# Power.net
KiCad netlist of a schematic drawn in Altium Designer
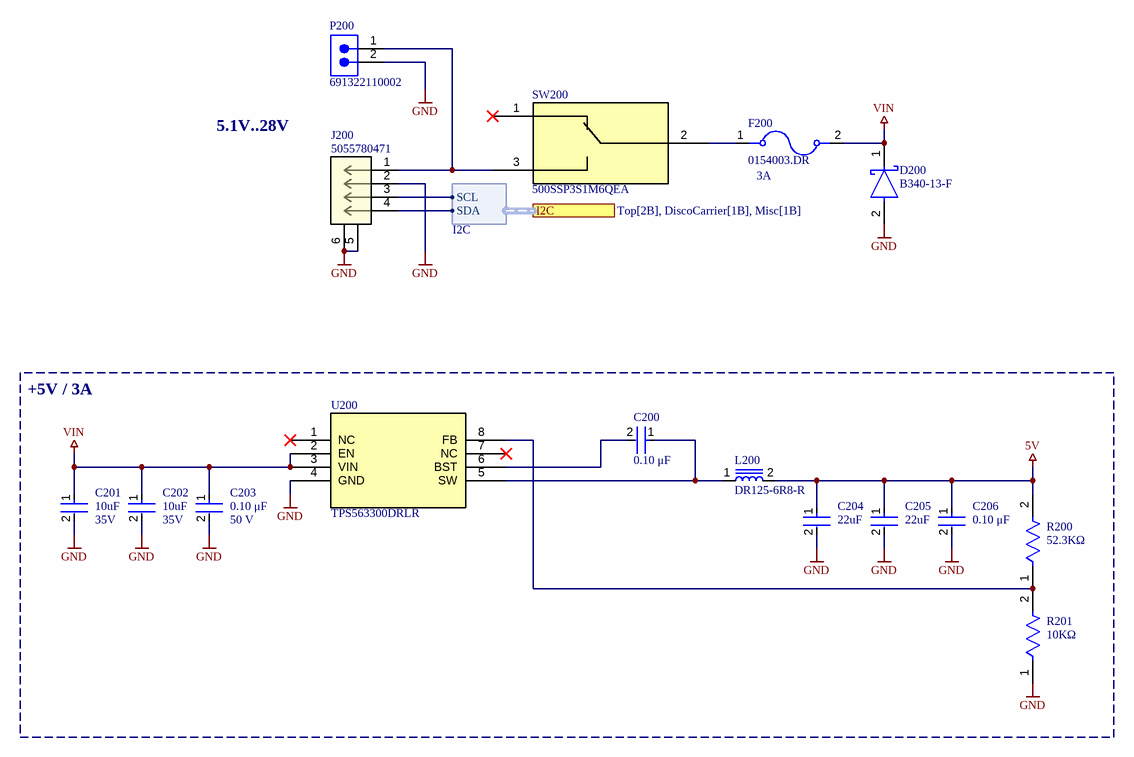
[diagram p0: Power.SchDoc]

(export (version "E")
  (design (tool "Eeschema 10.0.6"))
  (components
    (comp (ref "C200")
      (value "0.10 μF")
      (footprint "FP-C0603C-CF-MFG")
      (description "CAP CER 0.1UF 50V 20% X7R 0603")
      (fields
        (field (name "MANUFACTURER PART NUMBER") "C0603C104M5RACTU")
        (field (name "MANUFACTURER") "KEMET")
      )
      (libsource (lib "Altium Content Vault") (part "b4654b650e69147ec39a6b967a45e02"))
    )
    (comp (ref "C201")
      (value "GRT31CR6YA106KE01L")
      (footprint "FP-GRT31C-0_2-IPC_A")
      (description "Multi-Layer Ceramic Capacitor 10uF 35V X5R ±10% 1206 Emboss T/R")
      (fields
        (field (name "CAPACITANCE") "10uF")
        (field (name "TOLERANCE") "10%")
        (field (name "VOLTAGE RATING") "35V")
      )
      (libsource (lib "Altium Content Vault") (part "02cd4be3c70576c341d710602a673aa"))
    )
    (comp (ref "C202")
      (value "GRT31CR6YA106KE01L")
      (footprint "FP-GRT31C-0_2-IPC_A")
      (description "Multi-Layer Ceramic Capacitor 10uF 35V X5R ±10% 1206 Emboss T/R")
      (fields
        (field (name "CAPACITANCE") "10uF")
        (field (name "TOLERANCE") "10%")
        (field (name "VOLTAGE RATING") "35V")
      )
      (libsource (lib "Altium Content Vault") (part "02cd4be3c70576c341d710602a673aa"))
    )
    (comp (ref "C203")
      (value "0.10 μF")
      (footprint "FP-C0603C-CF-MFG")
      (description "CAP CER 0.1UF 50V 20% X7R 0603")
      (fields
        (field (name "VOLTAGE RATING") "50 V")
        (field (name "MANUFACTURER PART NUMBER") "C0603C104M5RACTU")
        (field (name "MANUFACTURER") "KEMET")
      )
      (libsource (lib "Altium Content Vault") (part "b4654b650e69147ec39a6b967a45e02"))
    )
    (comp (ref "C204")
      (value "GRM319R61C226ME15D")
      (footprint "FP-GRM319-0_15-IPC_C")
      (description "Chip Multilayer Ceramic Capacitors for General Purpose, 1206, 22uF, X5R, 15%, 20%, 16V")
      (fields (field (name "TOLERANCE") "20%") (field (name "CAPACITANCE") "22uF"))
      (libsource (lib "Altium Content Vault") (part "b4654b650e69147ec39a6b967a45e02"))
    )
    (comp (ref "C205")
      (value "GRM319R61C226ME15D")
      (footprint "FP-GRM319-0_15-IPC_C")
      (description "Chip Multilayer Ceramic Capacitors for General Purpose, 1206, 22uF, X5R, 15%, 20%, 16V")
      (fields (field (name "TOLERANCE") "20%") (field (name "CAPACITANCE") "22uF"))
      (libsource (lib "Altium Content Vault") (part "b4654b650e69147ec39a6b967a45e02"))
    )
    (comp (ref "C206")
      (value "0.10 μF")
      (footprint "FP-C0603C-CF-MFG")
      (description "CAP CER 0.1UF 50V 20% X7R 0603")
      (fields
        (field (name "MANUFACTURER PART NUMBER") "C0603C104M5RACTU")
        (field (name "MANUFACTURER") "KEMET")
      )
      (libsource (lib "Altium Content Vault") (part "b4654b650e69147ec39a6b967a45e02"))
    )
    (comp (ref "D200")
      (value "B340-13-F")
      (footprint "FP-SMC-MFG")
      (description "DIODE SCHOTTKY 40V 3A SMC")
      (fields
        (field (name "MANUFACTURER") "Diodes Inc.")
        (field (name "OCTOPART") "https://octopart.com/b340-13-f-diodes+inc.-325814")
      )
      (libsource (lib "Altium Content Vault") (part "1d6ec82d83fb6aee721767c19dac4b9"))
    )
    (comp (ref "F200")
      (value "0154003.DR")
      (footprint "FUSE_0154003.DR")
      (description "Nano2 SMD FF submin fuse w/holder, 3A ¦ Littelfuse 0154003.DR")
      (fields (field (name "ALTIUM_VALUE") "3A") (field (name "MF") "Littelfuse Inc."))
      (libsource (lib "robby") (part "0154003.DR"))
    )
    (comp (ref "J200")
      (value "5055780471")
      (footprint "CONN_505578_04_MOL")
      (fields (field (name "COPYRIGHT") "Copyright (C) 2025 Ultra Librarian. All rights reserved."))
      (libsource (lib "robby") (part "5055780471"))
    )
    (comp (ref "L200")
      (value "DR125-6R8-R")
      (footprint "robby:INDM1250X1250X600")
      (description "Inductor Power Shielded Drum Core 3.084u(OCL)H/3.3uH 20% 100KHz Ferrite 9.26A 6.3mOhm DCR T/R")
      (libsource (lib "robby") (part "DR125-6R8-R"))
    )
    (comp (ref "P200")
      (value "691322110002")
      (footprint "691322110002")
      (fields (field (name "VOLTAGE") "300V"))
      (libsource (lib "Altium Content Vault") (part "TBL - 1R - 02P - Male"))
    )
    (comp (ref "R200")
      (value "52.3KΩ")
      (footprint "FP-RT0603-MFG")
      (description "RES SMD 52.3K OHM 1% 1/10W 0603")
      (fields
        (field (name "MANUFACTURER PART NUMBER") "RT0603FRE0752K3L")
        (field (name "MANUFACTURER") "Yageo")
      )
      (libsource (lib "Altium Content Vault") (part "1029c3af85768c4190bb7ad29bc67b5"))
    )
    (comp (ref "R201")
      (value "10KΩ")
      (footprint "FP-RT0603-MFG")
      (description "RES SMD 10K OHM 1% 1/10W 0603")
      (fields
        (field (name "MANUFACTURER") "Yageo")
        (field (name "OCTOPART") "https://octopart.com/rt0603fre0710kl-yageo-40009243")
      )
      (libsource (lib "Altium Content Vault") (part "1029c3af85768c4190bb7ad29bc67b5"))
    )
    (comp (ref "SW200")
      (value "500SSP3S1M6QEA")
      (footprint "SW3_500SSP3S1M6QEA_EWI")
      (description "No Description Available")
      (fields (field (name "COPYRIGHT") "Copyright (C) 2025 Ultra Librarian. All rights reserved."))
      (libsource (lib "robby") (part "500SSP3S1M6QEA"))
    )
    (comp (ref "U200")
      (value "TPS563300DRLR")
      (footprint "SOT5X3-8_DRL_TEX")
      (description "3.8-V to 28-V Input, 3-A synchronous buck converter in SOT-583 package 8-SOT-5X3 -40 to 150")
      (fields (field (name "COPYRIGHT") "Copyright (C) 2025 Ultra Librarian. All rights reserved."))
      (libsource (lib "robby") (part "TPS563300DRLR"))
    )
  )
  (nets
    (net (code "2") (name "/SCL") (class "Default")
      (node (ref "J200") (pin "3") (pinfunction "3_3") (pintype "passive"))
    )
    (net (code "3") (name "/SDA") (class "Default")
      (node (ref "J200") (pin "4") (pinfunction "4_4") (pintype "passive"))
    )
    (net (code "5") (name "5V") (class "Default")
      (node (ref "C204") (pin "1") (pinfunction "1_1") (pintype "passive"))
      (node (ref "C205") (pin "1") (pinfunction "1_1") (pintype "passive"))
      (node (ref "C206") (pin "1") (pinfunction "1_1") (pintype "passive"))
      (node (ref "L200") (pin "2") (pinfunction "2_2") (pintype "passive"))
      (node (ref "R200") (pin "2") (pinfunction "2_2") (pintype "passive"))
    )
    (net (code "6") (name "GND") (class "Default")
      (node (ref "C201") (pin "2") (pinfunction "2_2") (pintype "passive"))
      (node (ref "C202") (pin "2") (pinfunction "2_2") (pintype "passive"))
      (node (ref "C203") (pin "2") (pinfunction "2_2") (pintype "passive"))
      (node (ref "C204") (pin "2") (pinfunction "2_2") (pintype "passive"))
      (node (ref "C205") (pin "2") (pinfunction "2_2") (pintype "passive"))
      (node (ref "C206") (pin "2") (pinfunction "2_2") (pintype "passive"))
      (node (ref "D200") (pin "2") (pinfunction "A_2") (pintype "passive"))
      (node (ref "J200") (pin "2") (pinfunction "2_2") (pintype "passive"))
      (node (ref "J200") (pin "5") (pinfunction "5_5") (pintype "passive"))
      (node (ref "J200") (pin "6") (pinfunction "6_6") (pintype "passive"))
      (node (ref "P200") (pin "2") (pinfunction "2_2") (pintype "passive"))
      (node (ref "R201") (pin "1") (pinfunction "1_1") (pintype "passive"))
      (node (ref "U200") (pin "4") (pinfunction "GND_4") (pintype "power_in"))
    )
    (net (code "7") (name "Net-(F200-Pad1)") (class "Default")
      (node (ref "F200") (pin "1") (pinfunction "1_1") (pintype "passive"))
      (node (ref "SW200") (pin "2") (pinfunction "2_2") (pintype "passive"))
    )
    (net (code "8") (name "Net-(J200-Pad1)") (class "Default")
      (node (ref "J200") (pin "1") (pinfunction "1_1") (pintype "passive"))
      (node (ref "P200") (pin "1") (pinfunction "1_1") (pintype "passive"))
      (node (ref "SW200") (pin "3") (pinfunction "3_3") (pintype "passive"))
    )
    (net (code "9") (name "Net-(U200-BST)") (class "Default")
      (node (ref "C200") (pin "2") (pinfunction "2_2") (pintype "passive"))
      (node (ref "U200") (pin "6") (pinfunction "BST_6") (pintype "power_in"))
    )
    (net (code "10") (name "Net-(U200-FB)") (class "Default")
      (node (ref "R200") (pin "1") (pinfunction "1_1") (pintype "passive"))
      (node (ref "R201") (pin "2") (pinfunction "2_2") (pintype "passive"))
      (node (ref "U200") (pin "8") (pinfunction "FB_8") (pintype "passive"))
    )
    (net (code "11") (name "Net-(U200-SW)") (class "Default")
      (node (ref "C200") (pin "1") (pinfunction "1_1") (pintype "passive"))
      (node (ref "L200") (pin "1") (pinfunction "1_1") (pintype "passive"))
      (node (ref "U200") (pin "5") (pinfunction "SW_5") (pintype "power_in"))
    )
    (net (code "12") (name "VIN") (class "Default")
      (node (ref "C201") (pin "1") (pinfunction "1_1") (pintype "passive"))
      (node (ref "C202") (pin "1") (pinfunction "1_1") (pintype "passive"))
      (node (ref "C203") (pin "1") (pinfunction "1_1") (pintype "passive"))
      (node (ref "D200") (pin "1") (pinfunction "C_1") (pintype "passive"))
      (node (ref "F200") (pin "2") (pinfunction "2_2") (pintype "passive"))
      (node (ref "U200") (pin "2") (pinfunction "EN_2") (pintype "passive"))
      (node (ref "U200") (pin "3") (pinfunction "VIN_3") (pintype "power_in"))
    )
    (net (code "13") (name "unconnected-(SW200-Pad1)") (class "Default")
      (node (ref "SW200") (pin "1") (pinfunction "1_1") (pintype "passive+no_connect"))
    )
    (net (code "14") (name "unconnected-(U200-NC-Pad1)") (class "Default")
      (node (ref "U200") (pin "1") (pinfunction "NC_1") (pintype "passive+no_connect"))
    )
    (net (code "15") (name "unconnected-(U200-NC-Pad7)") (class "Default")
      (node (ref "U200") (pin "7") (pinfunction "NC_7") (pintype "passive+no_connect"))
    )
  )
)
